# Slew_and_Hold_v1.net
KiCad netlist of a schematic drawn in EAGLE
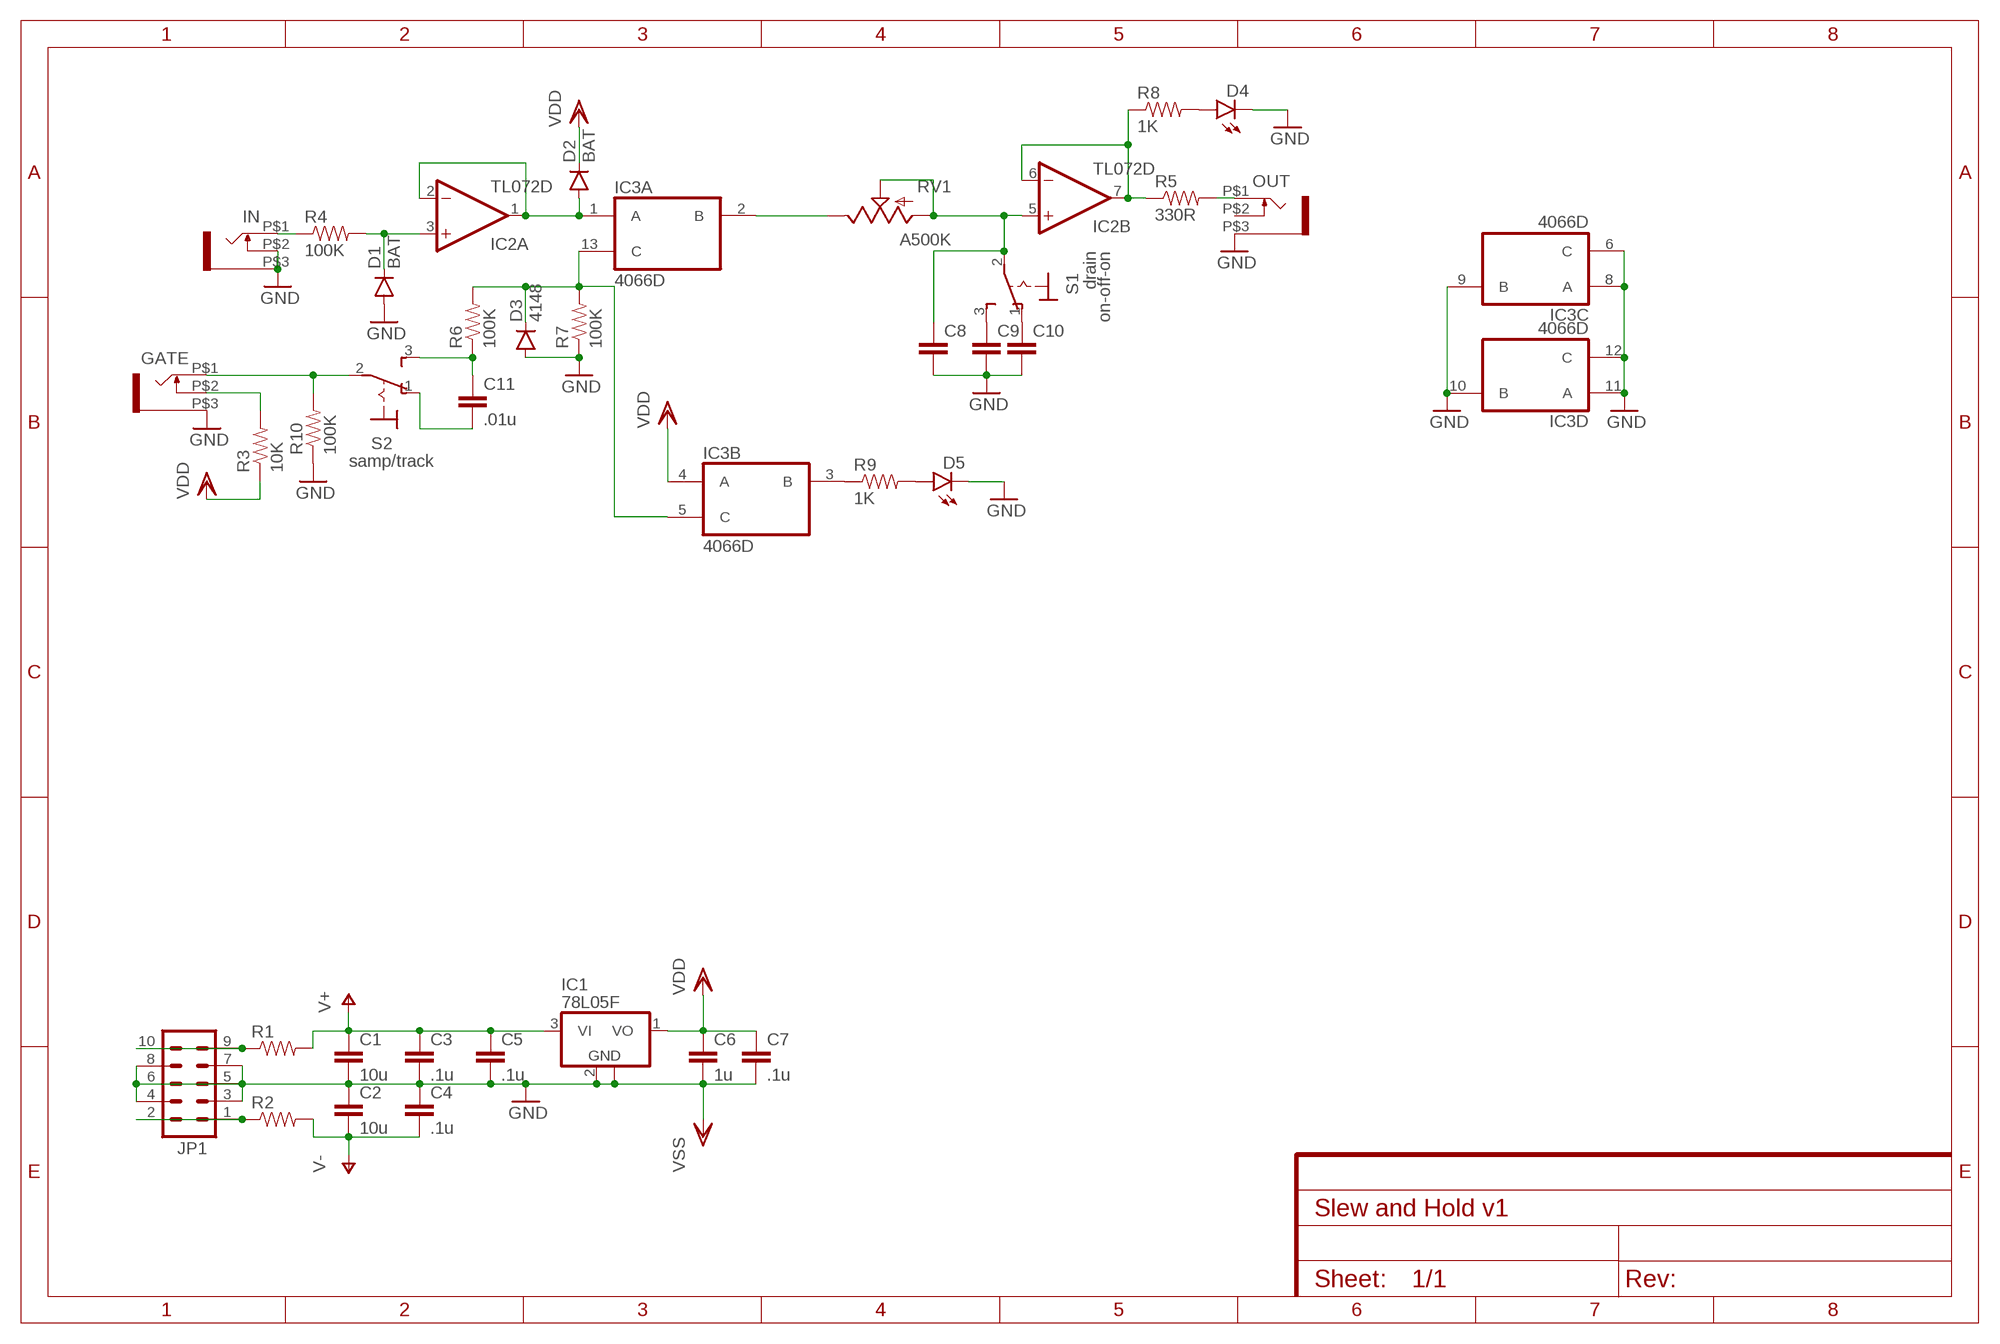
[diagram p0: schematic, sheet 1]

(export (version "E")
  (design (tool "Eeschema 10.0.6"))
  (components
    (comp (ref "C1")
      (value "10u")
      (footprint "eagle-import:1206")
      (libsource (lib "eagle-import") (part "CAP1206"))
    )
    (comp (ref "C2")
      (value "10u")
      (footprint "eagle-import:1206")
      (libsource (lib "eagle-import") (part "CAP1206"))
    )
    (comp (ref "C3")
      (value ".1u")
      (footprint "eagle-import:0805")
      (libsource (lib "eagle-import") (part "CAP0805"))
    )
    (comp (ref "C4")
      (value ".1u")
      (footprint "eagle-import:0805")
      (libsource (lib "eagle-import") (part "CAP0805"))
    )
    (comp (ref "C5")
      (value ".1u")
      (footprint "eagle-import:0805")
      (libsource (lib "eagle-import") (part "CAP0805"))
    )
    (comp (ref "C6")
      (value "1u")
      (footprint "eagle-import:0805")
      (libsource (lib "eagle-import") (part "CAP0805"))
    )
    (comp (ref "C7")
      (value ".1u")
      (footprint "eagle-import:0805")
      (libsource (lib "eagle-import") (part "CAP0805"))
    )
    (comp (ref "C8")
      (value "CAP0805")
      (footprint "eagle-import:0805")
      (libsource (lib "eagle-import") (part "CAP0805"))
    )
    (comp (ref "C9")
      (value "CAP0805")
      (footprint "eagle-import:0805")
      (libsource (lib "eagle-import") (part "CAP0805"))
    )
    (comp (ref "C10")
      (value "CAP0805")
      (footprint "eagle-import:0805")
      (libsource (lib "eagle-import") (part "CAP0805"))
    )
    (comp (ref "C11")
      (value ".01u")
      (footprint "eagle-import:0805")
      (libsource (lib "eagle-import") (part "CAP0805"))
    )
    (comp (ref "D1")
      (value "BAT")
      (footprint "eagle-import:SOD-123")
      (libsource (lib "eagle-import") (part "DIODESOD123"))
    )
    (comp (ref "D2")
      (value "BAT")
      (footprint "eagle-import:SOD-123")
      (libsource (lib "eagle-import") (part "DIODESOD123"))
    )
    (comp (ref "D3")
      (value "4148")
      (footprint "eagle-import:SOD-123")
      (libsource (lib "eagle-import") (part "DIODESOD123"))
    )
    (comp (ref "D4")
      (value "LED3MM")
      (footprint "eagle-import:LED3MM")
      (libsource (lib "eagle-import") (part "LED3MM"))
    )
    (comp (ref "D5")
      (value "LED3MM")
      (footprint "eagle-import:LED3MM")
      (libsource (lib "eagle-import") (part "LED3MM"))
    )
    (comp (ref "GATE")
      (value "WQP-PJ301M-12_JACK")
      (footprint "eagle-import:WQP-PJ301M-12_JACK")
      (libsource (lib "eagle-import") (part "WQP-PJ301M-12_JACK"))
    )
    (comp (ref "IC1")
      (value "78L05F")
      (footprint "eagle-import:SOT89")
      (libsource (lib "eagle-import") (part "78LF05"))
    )
    (comp (ref "IC2")
      (value "TL072D")
      (footprint "eagle-import:SO08")
      (libsource (lib "eagle-import") (part "TL072D"))
    )
    (comp (ref "IC3")
      (value "4066D")
      (footprint "eagle-import:SO14")
      (libsource (lib "eagle-import") (part "4066D"))
    )
    (comp (ref "IN")
      (value "WQP-PJ301M-12_JACK")
      (footprint "eagle-import:WQP-PJ301M-12_JACK")
      (libsource (lib "eagle-import") (part "WQP-PJ301M-12_JACK"))
    )
    (comp (ref "JP1")
      (value "M05X2PTH")
      (footprint "eagle-import:AVR_ICSP")
      (libsource (lib "eagle-import") (part "M05X2PTH"))
    )
    (comp (ref "OUT")
      (value "WQP-PJ301M-12_JACK")
      (footprint "eagle-import:WQP-PJ301M-12_JACK")
      (libsource (lib "eagle-import") (part "WQP-PJ301M-12_JACK"))
    )
    (comp (ref "R1")
      (value "RESISTOR0805-RES")
      (footprint "eagle-import:0805")
      (libsource (lib "eagle-import") (part "RESISTOR0805-RES"))
    )
    (comp (ref "R2")
      (value "RESISTOR0805-RES")
      (footprint "eagle-import:0805")
      (libsource (lib "eagle-import") (part "RESISTOR0805-RES"))
    )
    (comp (ref "R3")
      (value "10K")
      (footprint "eagle-import:0805")
      (libsource (lib "eagle-import") (part "RESISTOR0805-RES"))
    )
    (comp (ref "R4")
      (value "100K")
      (footprint "eagle-import:0805")
      (libsource (lib "eagle-import") (part "RESISTOR0805-RES"))
    )
    (comp (ref "R5")
      (value "330R")
      (footprint "eagle-import:0805")
      (libsource (lib "eagle-import") (part "RESISTOR0805-RES"))
    )
    (comp (ref "R6")
      (value "100K")
      (footprint "eagle-import:0805")
      (libsource (lib "eagle-import") (part "RESISTOR0805-RES"))
    )
    (comp (ref "R7")
      (value "100K")
      (footprint "eagle-import:0805")
      (libsource (lib "eagle-import") (part "RESISTOR0805-RES"))
    )
    (comp (ref "R8")
      (value "1K")
      (footprint "eagle-import:0805")
      (libsource (lib "eagle-import") (part "RESISTOR0805-RES"))
    )
    (comp (ref "R9")
      (value "1K")
      (footprint "eagle-import:0805")
      (libsource (lib "eagle-import") (part "RESISTOR0805-RES"))
    )
    (comp (ref "R10")
      (value "100K")
      (footprint "eagle-import:0805")
      (libsource (lib "eagle-import") (part "RESISTOR0805-RES"))
    )
    (comp (ref "RV1")
      (value "A500K")
      (footprint "eagle-import:ALPS_POT")
      (libsource (lib "eagle-import") (part "POT"))
    )
    (comp (ref "S1")
      (value "drain")
      (footprint "eagle-import:M9040P")
      (libsource (lib "eagle-import") (part "M9040P"))
    )
    (comp (ref "S2")
      (value "samp/track")
      (footprint "eagle-import:M9040P")
      (libsource (lib "eagle-import") (part "M9040P"))
    )
  )
  (nets
    (net (code "1") (name "GND") (class "Default")
      (node (ref "C1") (pin "2") (pinfunction "2_2") (pintype "passive"))
      (node (ref "C10") (pin "2") (pinfunction "2_2") (pintype "passive"))
      (node (ref "C2") (pin "1") (pinfunction "1_1") (pintype "passive"))
      (node (ref "C3") (pin "2") (pinfunction "2_2") (pintype "passive"))
      (node (ref "C4") (pin "1") (pinfunction "1_1") (pintype "passive"))
      (node (ref "C5") (pin "2") (pinfunction "2_2") (pintype "passive"))
      (node (ref "C6") (pin "2") (pinfunction "2_2") (pintype "passive"))
      (node (ref "C7") (pin "2") (pinfunction "2_2") (pintype "passive"))
      (node (ref "C8") (pin "2") (pinfunction "2_2") (pintype "passive"))
      (node (ref "C9") (pin "2") (pinfunction "2_2") (pintype "passive"))
      (node (ref "D1") (pin "A") (pinfunction "A_A") (pintype "passive"))
      (node (ref "D3") (pin "A") (pinfunction "A_A") (pintype "passive"))
      (node (ref "D4") (pin "K") (pinfunction "C_K") (pintype "passive"))
      (node (ref "D5") (pin "K") (pinfunction "C_K") (pintype "passive"))
      (node (ref "GATE") (pin "P$3") (pinfunction "1_P$3") (pintype "passive"))
      (node (ref "IC1") (pin "2") (pinfunction "GND_2") (pintype "passive"))
      (node (ref "IC1") (pin "2@1") (pinfunction "GND_2@1") (pintype "passive"))
      (node (ref "IC3") (pin "10") (pinfunction "B_10") (pintype "tri_state"))
      (node (ref "IC3") (pin "11") (pinfunction "A_11") (pintype "tri_state"))
      (node (ref "IC3") (pin "12") (pinfunction "C_12") (pintype "input"))
      (node (ref "IC3") (pin "6") (pinfunction "C_6") (pintype "input"))
      (node (ref "IC3") (pin "8") (pinfunction "A_8") (pintype "tri_state"))
      (node (ref "IC3") (pin "9") (pinfunction "B_9") (pintype "tri_state"))
      (node (ref "IN") (pin "P$2") (pinfunction "3_P$2") (pintype "passive"))
      (node (ref "IN") (pin "P$3") (pinfunction "1_P$3") (pintype "passive"))
      (node (ref "JP1") (pin "3") (pinfunction "3_3") (pintype "passive"))
      (node (ref "JP1") (pin "4") (pinfunction "4_4") (pintype "passive"))
      (node (ref "JP1") (pin "5") (pinfunction "5_5") (pintype "passive"))
      (node (ref "JP1") (pin "6") (pinfunction "6_6") (pintype "passive"))
      (node (ref "JP1") (pin "7") (pinfunction "7_7") (pintype "passive"))
      (node (ref "JP1") (pin "8") (pinfunction "8_8") (pintype "passive"))
      (node (ref "OUT") (pin "P$3") (pinfunction "1_P$3") (pintype "passive"))
      (node (ref "R10") (pin "1") (pinfunction "1_1") (pintype "passive"))
      (node (ref "R7") (pin "1") (pinfunction "1_1") (pintype "passive"))
    )
    (net (code "2") (name "Net-(D4-PadA)") (class "Default")
      (node (ref "D4") (pin "A") (pinfunction "A_A") (pintype "passive"))
      (node (ref "R8") (pin "2") (pinfunction "2_2") (pintype "passive"))
    )
    (net (code "3") (name "Net-(D5-PadA)") (class "Default")
      (node (ref "D5") (pin "A") (pinfunction "A_A") (pintype "passive"))
      (node (ref "R9") (pin "2") (pinfunction "2_2") (pintype "passive"))
    )
    (net (code "4") (name "Net-(GATE-2)") (class "Default")
      (node (ref "GATE") (pin "P$1") (pinfunction "2_P$1") (pintype "passive"))
      (node (ref "R10") (pin "2") (pinfunction "2_2") (pintype "passive"))
      (node (ref "S2") (pin "2") (pinfunction "P_2") (pintype "passive"))
    )
    (net (code "5") (name "Net-(GATE-3)") (class "Default")
      (node (ref "GATE") (pin "P$2") (pinfunction "3_P$2") (pintype "passive"))
      (node (ref "R3") (pin "2") (pinfunction "2_2") (pintype "passive"))
    )
    (net (code "6") (name "Net-(IC2A-+IN)") (class "Default")
      (node (ref "D1") (pin "C") (pinfunction "C_C") (pintype "passive"))
      (node (ref "IC2") (pin "3") (pinfunction "+IN_3") (pintype "input"))
      (node (ref "R4") (pin "2") (pinfunction "2_2") (pintype "passive"))
    )
    (net (code "7") (name "Net-(IC2A--IN)") (class "Default")
      (node (ref "D2") (pin "A") (pinfunction "A_A") (pintype "passive"))
      (node (ref "IC2") (pin "1") (pinfunction "OUT_1") (pintype "output"))
      (node (ref "IC2") (pin "2") (pinfunction "-IN_2") (pintype "input"))
      (node (ref "IC3") (pin "1") (pinfunction "A_1") (pintype "tri_state"))
    )
    (net (code "8") (name "Net-(IC2B-+IN)") (class "Default")
      (node (ref "C8") (pin "1") (pinfunction "1_1") (pintype "passive"))
      (node (ref "IC2") (pin "5") (pinfunction "+IN_5") (pintype "input"))
      (node (ref "RV1") (pin "P$2") (pinfunction "S_P$2") (pintype "passive"))
      (node (ref "RV1") (pin "P$3") (pinfunction "A_P$3") (pintype "passive"))
      (node (ref "S1") (pin "2") (pinfunction "P_2") (pintype "passive"))
    )
    (net (code "9") (name "Net-(IC2B--IN)") (class "Default")
      (node (ref "IC2") (pin "6") (pinfunction "-IN_6") (pintype "input"))
      (node (ref "IC2") (pin "7") (pinfunction "OUT_7") (pintype "output"))
      (node (ref "R5") (pin "1") (pinfunction "1_1") (pintype "passive"))
      (node (ref "R8") (pin "1") (pinfunction "1_1") (pintype "passive"))
    )
    (net (code "10") (name "Net-(IC3A-B)") (class "Default")
      (node (ref "IC3") (pin "2") (pinfunction "B_2") (pintype "tri_state"))
      (node (ref "RV1") (pin "P$1") (pinfunction "E_P$1") (pintype "passive"))
    )
    (net (code "11") (name "Net-(IC3A-C)") (class "Default")
      (node (ref "D3") (pin "C") (pinfunction "C_C") (pintype "passive"))
      (node (ref "IC3") (pin "13") (pinfunction "C_13") (pintype "input"))
      (node (ref "IC3") (pin "5") (pinfunction "C_5") (pintype "input"))
      (node (ref "R6") (pin "2") (pinfunction "2_2") (pintype "passive"))
      (node (ref "R7") (pin "2") (pinfunction "2_2") (pintype "passive"))
    )
    (net (code "12") (name "Net-(IC3B-B)") (class "Default")
      (node (ref "IC3") (pin "3") (pinfunction "B_3") (pintype "tri_state"))
      (node (ref "R9") (pin "1") (pinfunction "1_1") (pintype "passive"))
    )
    (net (code "13") (name "Net-(IN-2)") (class "Default")
      (node (ref "IN") (pin "P$1") (pinfunction "2_P$1") (pintype "passive"))
      (node (ref "R4") (pin "1") (pinfunction "1_1") (pintype "passive"))
    )
    (net (code "14") (name "Net-(JP1-Pad1)") (class "Default")
      (node (ref "JP1") (pin "1") (pinfunction "1_1") (pintype "passive"))
      (node (ref "JP1") (pin "2") (pinfunction "2_2") (pintype "passive"))
      (node (ref "R2") (pin "1") (pinfunction "1_1") (pintype "passive"))
    )
    (net (code "15") (name "Net-(JP1-Pad10)") (class "Default")
      (node (ref "JP1") (pin "10") (pinfunction "10_10") (pintype "passive"))
      (node (ref "JP1") (pin "9") (pinfunction "9_9") (pintype "passive"))
      (node (ref "R1") (pin "1") (pinfunction "1_1") (pintype "passive"))
    )
    (net (code "16") (name "Net-(OUT-2)") (class "Default")
      (node (ref "OUT") (pin "P$1") (pinfunction "2_P$1") (pintype "passive"))
      (node (ref "R5") (pin "2") (pinfunction "2_2") (pintype "passive"))
    )
    (net (code "17") (name "Net-(S1-O)") (class "Default")
      (node (ref "C10") (pin "1") (pinfunction "1_1") (pintype "passive"))
      (node (ref "S1") (pin "1") (pinfunction "O_1") (pintype "passive"))
    )
    (net (code "18") (name "Net-(S1-S)") (class "Default")
      (node (ref "C9") (pin "1") (pinfunction "1_1") (pintype "passive"))
      (node (ref "S1") (pin "3") (pinfunction "S_3") (pintype "passive"))
    )
    (net (code "19") (name "Net-(S2-O)") (class "Default")
      (node (ref "C11") (pin "2") (pinfunction "2_2") (pintype "passive"))
      (node (ref "S2") (pin "1") (pinfunction "O_1") (pintype "passive"))
    )
    (net (code "20") (name "Net-(S2-S)") (class "Default")
      (node (ref "C11") (pin "1") (pinfunction "1_1") (pintype "passive"))
      (node (ref "R6") (pin "1") (pinfunction "1_1") (pintype "passive"))
      (node (ref "S2") (pin "3") (pinfunction "S_3") (pintype "passive"))
    )
    (net (code "21") (name "V+") (class "Default")
      (node (ref "C1") (pin "1") (pinfunction "1_1") (pintype "passive"))
      (node (ref "C3") (pin "1") (pinfunction "1_1") (pintype "passive"))
      (node (ref "C5") (pin "1") (pinfunction "1_1") (pintype "passive"))
      (node (ref "IC1") (pin "3") (pinfunction "VI_3") (pintype "input"))
      (node (ref "R1") (pin "2") (pinfunction "2_2") (pintype "passive"))
    )
    (net (code "22") (name "V-") (class "Default")
      (node (ref "C2") (pin "2") (pinfunction "2_2") (pintype "passive"))
      (node (ref "C4") (pin "2") (pinfunction "2_2") (pintype "passive"))
      (node (ref "R2") (pin "2") (pinfunction "2_2") (pintype "passive"))
    )
    (net (code "23") (name "VDD") (class "Default")
      (node (ref "C6") (pin "1") (pinfunction "1_1") (pintype "passive"))
      (node (ref "C7") (pin "1") (pinfunction "1_1") (pintype "passive"))
      (node (ref "D2") (pin "C") (pinfunction "C_C") (pintype "passive"))
      (node (ref "IC1") (pin "1") (pinfunction "VO_1") (pintype "passive"))
      (node (ref "IC3") (pin "4") (pinfunction "A_4") (pintype "tri_state"))
      (node (ref "R3") (pin "1") (pinfunction "1_1") (pintype "passive"))
    )
    (net (code "24") (name "unconnected-(OUT-3-PadP$2)") (class "Default")
      (node (ref "OUT") (pin "P$2") (pinfunction "3_P$2") (pintype "passive"))
    )
  )
)
